# AUDIO.net
KiCad netlist of a schematic drawn in Altium Designer
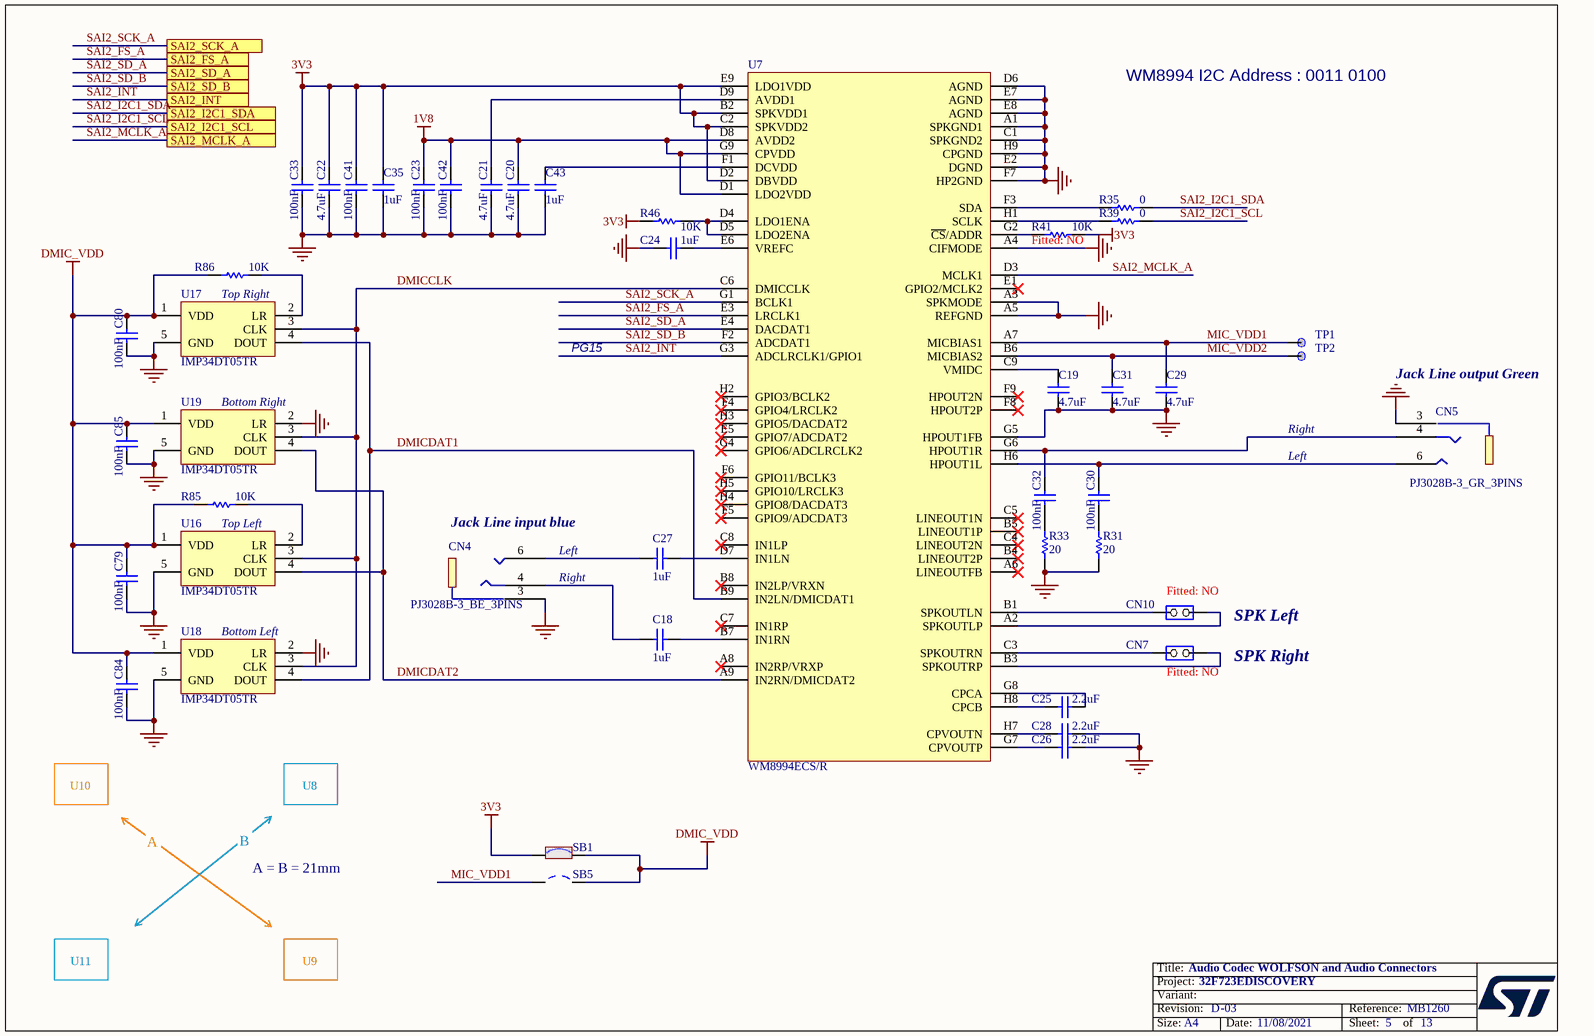
[diagram p0: AUDIO.SchDoc]

(export (version "E")
  (design (tool "Eeschema 10.0.6"))
  (components
    (comp (ref "C18")
      (value "1uF")
      (footprint "0603C")
      (description "Capacitor,1uF,16V,X5R,10%,0603,YAGEO")
      (libsource (lib "MCD_TOOLS_CAPACITOR") (part "Cap_1uF_X5R_10%_0603"))
    )
    (comp (ref "C19")
      (value "4.7uF")
      (footprint "0603C")
      (description "Capacitor,4.7uF,16V, X5R,10%,0603,YAGEO")
      (libsource (lib "MCD_TOOLS") (part "Cap_4.7uF_X5R_10%_0603"))
    )
    (comp (ref "C20")
      (value "4.7uF")
      (footprint "0603C")
      (description "Capacitor,4.7uF,16V, X5R,10%,0603,YAGEO")
      (libsource (lib "MCD_TOOLS") (part "Cap_4.7uF_X5R_10%_0603"))
    )
    (comp (ref "C21")
      (value "4.7uF")
      (footprint "0603C")
      (description "Capacitor,4.7uF,16V, X5R,10%,0603,YAGEO")
      (libsource (lib "MCD_TOOLS") (part "Cap_4.7uF_X5R_10%_0603"))
    )
    (comp (ref "C22")
      (value "4.7uF")
      (footprint "0603C")
      (description "Capacitor,4.7uF,16V, X5R,10%,0603,YAGEO")
      (libsource (lib "MCD_TOOLS") (part "Cap_4.7uF_X5R_10%_0603"))
    )
    (comp (ref "C23")
      (value "100nF")
      (footprint "0402C")
      (description "Capacitor,100nF,16V,X7R,10%,0402,YAGEO")
      (libsource (lib "MCD_TOOLS") (part "Cap_100nF_X7R_10%_0402"))
    )
    (comp (ref "C24")
      (value "1uF")
      (footprint "0603C")
      (description "Capacitor,1uF,16V,X5R,10%,0603,YAGEO")
      (libsource (lib "MCD_TOOLS_CAPACITOR") (part "Cap_1uF_X5R_10%_0603"))
    )
    (comp (ref "C25")
      (value "2.2uF")
      (footprint "0603C")
      (description "Capacitor,2.2uF,10V, X5R,10%,0603,YAGEO")
      (fields (field (name "Comment") "2.2uF_X5R_10%_0603"))
      (libsource (lib "MCD_TOOLS_CAPACITOR") (part "Cap_2.2uF_X5R_10%_0603"))
    )
    (comp (ref "C26")
      (value "2.2uF")
      (footprint "0603C")
      (description "Capacitor,2.2uF,10V, X5R,10%,0603,YAGEO")
      (fields (field (name "Comment") "2.2uF_X5R_10%_0603"))
      (libsource (lib "MCD_TOOLS_CAPACITOR") (part "Cap_2.2uF_X5R_10%_0603"))
    )
    (comp (ref "C27")
      (value "1uF")
      (footprint "0603C")
      (description "Capacitor,1uF,16V,X5R,10%,0603,YAGEO")
      (libsource (lib "MCD_TOOLS_CAPACITOR") (part "Cap_1uF_X5R_10%_0603"))
    )
    (comp (ref "C28")
      (value "2.2uF")
      (footprint "0603C")
      (description "Capacitor,2.2uF,10V, X5R,10%,0603,YAGEO")
      (fields (field (name "Comment") "2.2uF_X5R_10%_0603"))
      (libsource (lib "MCD_TOOLS_CAPACITOR") (part "Cap_2.2uF_X5R_10%_0603"))
    )
    (comp (ref "C29")
      (value "4.7uF")
      (footprint "0603C")
      (description "Capacitor,4.7uF,16V, X5R,10%,0603,YAGEO")
      (libsource (lib "MCD_TOOLS") (part "Cap_4.7uF_X5R_10%_0603"))
    )
    (comp (ref "C30")
      (value "100nF")
      (footprint "0402C")
      (description "Capacitor,100nF,16V,X7R,10%,0402,YAGEO")
      (libsource (lib "MCD_TOOLS") (part "Cap_100nF_X7R_10%_0402"))
    )
    (comp (ref "C31")
      (value "4.7uF")
      (footprint "0603C")
      (description "Capacitor,4.7uF,16V, X5R,10%,0603,YAGEO")
      (libsource (lib "MCD_TOOLS") (part "Cap_4.7uF_X5R_10%_0603"))
    )
    (comp (ref "C32")
      (value "100nF")
      (footprint "0402C")
      (description "Capacitor,100nF,16V,X7R,10%,0402,YAGEO")
      (libsource (lib "MCD_TOOLS") (part "Cap_100nF_X7R_10%_0402"))
    )
    (comp (ref "C33")
      (value "100nF")
      (footprint "0402C")
      (description "Capacitor,100nF,16V,X7R,10%,0402,YAGEO")
      (libsource (lib "MCD_TOOLS") (part "Cap_100nF_X7R_10%_0402"))
    )
    (comp (ref "C35")
      (value "1uF")
      (footprint "0603C")
      (description "Capacitor,1uF,16V,X5R,10%,0603,YAGEO")
      (libsource (lib "MCD_TOOLS_CAPACITOR") (part "Cap_1uF_X5R_10%_0603"))
    )
    (comp (ref "C41")
      (value "100nF")
      (footprint "0402C")
      (description "Capacitor,100nF,16V,X7R,10%,0402,YAGEO")
      (libsource (lib "MCD_TOOLS") (part "Cap_100nF_X7R_10%_0402"))
    )
    (comp (ref "C42")
      (value "100nF")
      (footprint "0402C")
      (description "Capacitor,100nF,16V,X7R,10%,0402,YAGEO")
      (libsource (lib "MCD_TOOLS") (part "Cap_100nF_X7R_10%_0402"))
    )
    (comp (ref "C43")
      (value "1uF")
      (footprint "0603C")
      (description "Capacitor,1uF,16V,X5R,10%,0603,YAGEO")
      (libsource (lib "MCD_TOOLS_CAPACITOR") (part "Cap_1uF_X5R_10%_0603"))
    )
    (comp (ref "C79")
      (value "100nF")
      (footprint "0402C")
      (description "Capacitor,100nF,16V,X7R,10%,0402,YAGEO")
      (libsource (lib "MCD_TOOLS") (part "Cap_100nF_X7R_10%_0402"))
    )
    (comp (ref "C80")
      (value "100nF")
      (footprint "0402C")
      (description "Capacitor,100nF,16V,X7R,10%,0402,YAGEO")
      (libsource (lib "MCD_TOOLS") (part "Cap_100nF_X7R_10%_0402"))
    )
    (comp (ref "C84")
      (value "100nF")
      (footprint "0402C")
      (description "Capacitor,100nF,16V,X7R,10%,0402,YAGEO")
      (libsource (lib "MCD_TOOLS") (part "Cap_100nF_X7R_10%_0402"))
    )
    (comp (ref "C85")
      (value "100nF")
      (footprint "0402C")
      (description "Capacitor,100nF,16V,X7R,10%,0402,YAGEO")
      (libsource (lib "MCD_TOOLS") (part "Cap_100nF_X7R_10%_0402"))
    )
    (comp (ref "CN4")
      (value "PJ3028B-3_BE_3PINS")
      (footprint "PJ3028B")
      (description "Connector Jack Stereo 3.5mm, female SMT, Blue (Line input)")
      (libsource (lib "MCD_TEMP_NPA") (part "PJ3028B-3_BE_3PINS"))
    )
    (comp (ref "CN5")
      (value "PJ3028B-3_GR_3PINS")
      (footprint "PJ3028B")
      (description "Connector Jack Stereo 3.5mm, female SMT, Green (Line output)")
      (libsource (lib "MCD_TEMP_NPA") (part "PJ3028B-3_GR_3PINS"))
    )
    (comp (ref "CN7")
      (value "JP2")
      (footprint "SIP2")
      (fields (field (name "FITTED") "NO"))
      (libsource (lib "MCD_TOOLS_CONNECTOR") (part "JP2"))
    )
    (comp (ref "CN10")
      (value "JP2")
      (footprint "SIP2")
      (fields (field (name "FITTED") "NO"))
      (libsource (lib "MCD_TOOLS_CONNECTOR") (part "JP2"))
    )
    (comp (ref "R31")
      (value "20")
      (footprint "0402R")
      (description "Resistor,20,0402,1%,YAGEO")
      (libsource (lib "MCD_TOOLS") (part "Res_20_1%_0402"))
    )
    (comp (ref "R33")
      (value "20")
      (footprint "0402R")
      (description "Resistor,20,0402,1%,YAGEO")
      (libsource (lib "MCD_TOOLS") (part "Res_20_1%_0402"))
    )
    (comp (ref "R35")
      (value "0")
      (footprint "0402R")
      (description "Resistor,0,0402,5%,YAGEO")
      (libsource (lib "MCD_TOOLS") (part "Res_0_5%_0402"))
    )
    (comp (ref "R39")
      (value "0")
      (footprint "0402R")
      (description "Resistor,0,0402,5%,YAGEO")
      (libsource (lib "MCD_TOOLS") (part "Res_0_5%_0402"))
    )
    (comp (ref "R41")
      (value "10K")
      (footprint "0402R")
      (description "Resistor,10K,0402,1%,YAGEO")
      (fields (field (name "FITTED") "NO"))
      (libsource (lib "MCD_TOOLS") (part "Res_10K_1%_0402"))
    )
    (comp (ref "R46")
      (value "10K")
      (footprint "0402R")
      (description "Resistor,10K,0402,1%,YAGEO")
      (libsource (lib "MCD_TOOLS") (part "Res_10K_1%_0402"))
    )
    (comp (ref "R85")
      (value "10K")
      (footprint "0402R")
      (description "Resistor,10K,0402,1%,YAGEO")
      (libsource (lib "MCD_TOOLS") (part "Res_10K_1%_0402"))
    )
    (comp (ref "R86")
      (value "10K")
      (footprint "0402R")
      (description "Resistor,10K,0402,1%,YAGEO")
      (libsource (lib "MCD_TOOLS") (part "Res_10K_1%_0402"))
    )
    (comp (ref "SB1")
      (value "Solder Bridge ON")
      (footprint "JP2_SMD")
      (libsource (lib "MCD_TOOLS") (part "SB_ON"))
    )
    (comp (ref "SB5")
      (value "Solder Bridge OFF")
      (footprint "JP2_SMD")
      (libsource (lib "MCD_TOOLS") (part "SB_OFF"))
    )
    (comp (ref "TP1")
      (value "TP")
      (footprint "TP_C40")
      (description "Test Point")
      (libsource (lib "MCD_TOOLS_CONNECTOR") (part "TP"))
    )
    (comp (ref "TP2")
      (value "TP")
      (footprint "TP_C40")
      (description "Test Point")
      (libsource (lib "MCD_TOOLS_CONNECTOR") (part "TP"))
    )
    (comp (ref "U7")
      (value "WM8994ECS/R")
      (footprint "BGA72_0R5_4R5X4")
      (description "Multi-Channel Audio Hub CODEC for Smartphones")
      (libsource (lib "MCD_TOOLS") (part "WM8994ECS/R"))
    )
    (comp (ref "U16")
      (value "IMP34DT05TR")
      (footprint "MP34DT01TR")
      (description "MEMS audio sensor, omnidirectional digital microphone")
      (libsource (lib "MCD_TOOLS_MISCELLANEOUS") (part "MP34DT01"))
    )
    (comp (ref "U17")
      (value "IMP34DT05TR")
      (footprint "MP34DT01TR")
      (description "MEMS audio sensor, omnidirectional digital microphone")
      (libsource (lib "MCD_TOOLS_MISCELLANEOUS") (part "MP34DT01"))
    )
    (comp (ref "U18")
      (value "IMP34DT05TR")
      (footprint "MP34DT01TR")
      (description "MEMS audio sensor, omnidirectional digital microphone")
      (libsource (lib "MCD_TOOLS_MISCELLANEOUS") (part "MP34DT01"))
    )
    (comp (ref "U19")
      (value "IMP34DT05TR")
      (footprint "MP34DT01TR")
      (description "MEMS audio sensor, omnidirectional digital microphone")
      (libsource (lib "MCD_TOOLS_MISCELLANEOUS") (part "MP34DT01"))
    )
  )
  (nets
    (net (code "1") (name "/DMICCLK") (class "Default")
      (node (ref "U16") (pin "3") (pinfunction "CLK_3") (pintype "passive"))
      (node (ref "U17") (pin "3") (pinfunction "CLK_3") (pintype "passive"))
      (node (ref "U18") (pin "3") (pinfunction "CLK_3") (pintype "passive"))
      (node (ref "U19") (pin "3") (pinfunction "CLK_3") (pintype "passive"))
      (node (ref "U7") (pin "C6") (pinfunction "DMICCLK_C6") (pintype "passive"))
    )
    (net (code "2") (name "/DMICDAT1") (class "Default")
      (node (ref "U17") (pin "4") (pinfunction "DOUT_4") (pintype "passive"))
      (node (ref "U18") (pin "4") (pinfunction "DOUT_4") (pintype "passive"))
      (node (ref "U7") (pin "B9") (pinfunction "IN2LN/DMICDAT1_B9") (pintype "passive"))
    )
    (net (code "3") (name "/DMICDAT2") (class "Default")
      (node (ref "U16") (pin "4") (pinfunction "DOUT_4") (pintype "passive"))
      (node (ref "U19") (pin "4") (pinfunction "DOUT_4") (pintype "passive"))
      (node (ref "U7") (pin "A9") (pinfunction "IN2RN/DMICDAT2_A9") (pintype "passive"))
    )
    (net (code "4") (name "/MIC_VDD1") (class "Default")
      (node (ref "C29") (pin "2") (pinfunction "2_2") (pintype "passive"))
      (node (ref "SB5") (pin "1") (pinfunction "1_1") (pintype "passive"))
      (node (ref "TP1") (pin "1") (pinfunction "1_1") (pintype "passive"))
      (node (ref "U7") (pin "A7") (pinfunction "MICBIAS1_A7") (pintype "passive"))
    )
    (net (code "5") (name "/MIC_VDD2") (class "Default")
      (node (ref "C31") (pin "2") (pinfunction "2_2") (pintype "passive"))
      (node (ref "TP2") (pin "1") (pinfunction "1_1") (pintype "passive"))
      (node (ref "U7") (pin "B6") (pinfunction "MICBIAS2_B6") (pintype "passive"))
    )
    (net (code "6") (name "/SAI2_FS_A") (class "Default")
      (node (ref "U7") (pin "E3") (pinfunction "LRCLK1_E3") (pintype "passive"))
    )
    (net (code "7") (name "/SAI2_I2C1_SCL") (class "Default")
      (node (ref "R39") (pin "1") (pinfunction "1_1") (pintype "passive"))
    )
    (net (code "8") (name "/SAI2_I2C1_SDA") (class "Default")
      (node (ref "R35") (pin "1") (pinfunction "1_1") (pintype "passive"))
    )
    (net (code "9") (name "/SAI2_INT") (class "Default")
      (node (ref "U7") (pin "G3") (pinfunction "ADCLRCLK1/GPIO1_G3") (pintype "passive"))
    )
    (net (code "10") (name "/SAI2_MCLK_A") (class "Default")
      (node (ref "U7") (pin "D3") (pinfunction "MCLK1_D3") (pintype "passive"))
    )
    (net (code "11") (name "/SAI2_SCK_A") (class "Default")
      (node (ref "U7") (pin "G1") (pinfunction "BCLK1_G1") (pintype "passive"))
    )
    (net (code "12") (name "/SAI2_SD_A") (class "Default")
      (node (ref "U7") (pin "E4") (pinfunction "DACDAT1_E4") (pintype "passive"))
    )
    (net (code "13") (name "/SAI2_SD_B") (class "Default")
      (node (ref "U7") (pin "F2") (pinfunction "ADCDAT1_F2") (pintype "passive"))
    )
    (net (code "14") (name "1V8") (class "Default")
      (node (ref "C20") (pin "1") (pinfunction "1_1") (pintype "passive"))
      (node (ref "C23") (pin "1") (pinfunction "1_1") (pintype "passive"))
      (node (ref "C42") (pin "1") (pinfunction "1_1") (pintype "passive"))
      (node (ref "U7") (pin "D1") (pinfunction "LDO2VDD_D1") (pintype "passive"))
      (node (ref "U7") (pin "D8") (pinfunction "AVDD2_D8") (pintype "passive"))
      (node (ref "U7") (pin "G9") (pinfunction "CPVDD_G9") (pintype "passive"))
    )
    (net (code "15") (name "3V3") (class "Default")
      (node (ref "C22") (pin "1") (pinfunction "1_1") (pintype "passive"))
      (node (ref "C33") (pin "1") (pinfunction "1_1") (pintype "passive"))
      (node (ref "C35") (pin "2") (pinfunction "2_2") (pintype "passive"))
      (node (ref "C41") (pin "1") (pinfunction "1_1") (pintype "passive"))
      (node (ref "R41") (pin "1") (pinfunction "1_1") (pintype "passive"))
      (node (ref "R46") (pin "2") (pinfunction "2_2") (pintype "passive"))
      (node (ref "SB1") (pin "1") (pinfunction "1_1") (pintype "passive"))
      (node (ref "U7") (pin "B2") (pinfunction "SPKVDD1_B2") (pintype "passive"))
      (node (ref "U7") (pin "C2") (pinfunction "SPKVDD2_C2") (pintype "passive"))
      (node (ref "U7") (pin "D2") (pinfunction "DBVDD_D2") (pintype "passive"))
      (node (ref "U7") (pin "E9") (pinfunction "LDO1VDD_E9") (pintype "passive"))
    )
    (net (code "16") (name "DMIC_VDD") (class "Default")
      (node (ref "C79") (pin "1") (pinfunction "1_1") (pintype "passive"))
      (node (ref "C80") (pin "1") (pinfunction "1_1") (pintype "passive"))
      (node (ref "C84") (pin "1") (pinfunction "1_1") (pintype "passive"))
      (node (ref "C85") (pin "1") (pinfunction "1_1") (pintype "passive"))
      (node (ref "R85") (pin "2") (pinfunction "2_2") (pintype "passive"))
      (node (ref "R86") (pin "2") (pinfunction "2_2") (pintype "passive"))
      (node (ref "SB1") (pin "2") (pinfunction "2_2") (pintype "passive"))
      (node (ref "SB5") (pin "2") (pinfunction "2_2") (pintype "passive"))
      (node (ref "U16") (pin "1") (pinfunction "VDD_1") (pintype "passive"))
      (node (ref "U17") (pin "1") (pinfunction "VDD_1") (pintype "passive"))
      (node (ref "U18") (pin "1") (pinfunction "VDD_1") (pintype "passive"))
      (node (ref "U19") (pin "1") (pinfunction "VDD_1") (pintype "passive"))
    )
    (net (code "17") (name "GND") (class "Default")
      (node (ref "C19") (pin "1") (pinfunction "1_1") (pintype "passive"))
      (node (ref "C20") (pin "2") (pinfunction "2_2") (pintype "passive"))
      (node (ref "C21") (pin "2") (pinfunction "2_2") (pintype "passive"))
      (node (ref "C22") (pin "2") (pinfunction "2_2") (pintype "passive"))
      (node (ref "C23") (pin "2") (pinfunction "2_2") (pintype "passive"))
      (node (ref "C24") (pin "2") (pinfunction "2_2") (pintype "passive"))
      (node (ref "C26") (pin "2") (pinfunction "2_2") (pintype "passive"))
      (node (ref "C28") (pin "2") (pinfunction "2_2") (pintype "passive"))
      (node (ref "C29") (pin "1") (pinfunction "1_1") (pintype "passive"))
      (node (ref "C31") (pin "1") (pinfunction "1_1") (pintype "passive"))
      (node (ref "C33") (pin "2") (pinfunction "2_2") (pintype "passive"))
      (node (ref "C35") (pin "1") (pinfunction "1_1") (pintype "passive"))
      (node (ref "C41") (pin "2") (pinfunction "2_2") (pintype "passive"))
      (node (ref "C42") (pin "2") (pinfunction "2_2") (pintype "passive"))
      (node (ref "C43") (pin "1") (pinfunction "1_1") (pintype "passive"))
      (node (ref "C79") (pin "2") (pinfunction "2_2") (pintype "passive"))
      (node (ref "C80") (pin "2") (pinfunction "2_2") (pintype "passive"))
      (node (ref "C84") (pin "2") (pinfunction "2_2") (pintype "passive"))
      (node (ref "C85") (pin "2") (pinfunction "2_2") (pintype "passive"))
      (node (ref "CN4") (pin "3") (pintype "passive"))
      (node (ref "CN5") (pin "3") (pintype "passive"))
      (node (ref "R31") (pin "2") (pinfunction "2_2") (pintype "passive"))
      (node (ref "R33") (pin "2") (pinfunction "2_2") (pintype "passive"))
      (node (ref "U16") (pin "5") (pinfunction "GND_5") (pintype "passive"))
      (node (ref "U17") (pin "5") (pinfunction "GND_5") (pintype "passive"))
      (node (ref "U18") (pin "2") (pinfunction "LR_2") (pintype "passive"))
      (node (ref "U18") (pin "5") (pinfunction "GND_5") (pintype "passive"))
      (node (ref "U19") (pin "2") (pinfunction "LR_2") (pintype "passive"))
      (node (ref "U19") (pin "5") (pinfunction "GND_5") (pintype "passive"))
      (node (ref "U7") (pin "A1") (pinfunction "SPKGND1_A1") (pintype "passive"))
      (node (ref "U7") (pin "A3") (pinfunction "SPKMODE_A3") (pintype "passive"))
      (node (ref "U7") (pin "A4") (pinfunction "CIFMODE_A4") (pintype "passive"))
      (node (ref "U7") (pin "A5") (pinfunction "REFGND_A5") (pintype "passive"))
      (node (ref "U7") (pin "C1") (pinfunction "SPKGND2_C1") (pintype "passive"))
      (node (ref "U7") (pin "D6") (pinfunction "AGND_D6") (pintype "passive"))
      (node (ref "U7") (pin "E2") (pinfunction "DGND_E2") (pintype "passive"))
      (node (ref "U7") (pin "E7") (pinfunction "AGND_E7") (pintype "passive"))
      (node (ref "U7") (pin "E8") (pinfunction "AGND_E8") (pintype "passive"))
      (node (ref "U7") (pin "F7") (pinfunction "HP2GND_F7") (pintype "passive"))
      (node (ref "U7") (pin "G5") (pinfunction "HPOUT1FB_G5") (pintype "passive"))
      (node (ref "U7") (pin "H9") (pinfunction "CPGND_H9") (pintype "passive"))
    )
    (net (code "18") (name "Net-(C18-Pad2)") (class "Default")
      (node (ref "C18") (pin "2") (pinfunction "2_2") (pintype "passive"))
      (node (ref "CN4") (pin "4") (pintype "passive"))
    )
    (net (code "19") (name "Net-(C27-Pad2)") (class "Default")
      (node (ref "C27") (pin "2") (pinfunction "2_2") (pintype "passive"))
      (node (ref "CN4") (pin "6") (pintype "passive"))
    )
    (net (code "20") (name "Net-(C30-Pad2)") (class "Default")
      (node (ref "C30") (pin "2") (pinfunction "2_2") (pintype "passive"))
      (node (ref "R31") (pin "1") (pinfunction "1_1") (pintype "passive"))
    )
    (net (code "21") (name "Net-(C32-Pad2)") (class "Default")
      (node (ref "C32") (pin "2") (pinfunction "2_2") (pintype "passive"))
      (node (ref "R33") (pin "1") (pinfunction "1_1") (pintype "passive"))
    )
    (net (code "22") (name "Net-(CN7-COMMON)") (class "Default")
      (node (ref "CN7") (pin "1") (pinfunction "COMMON_1") (pintype "passive"))
      (node (ref "U7") (pin "C3") (pinfunction "SPKOUTRN_C3") (pintype "passive"))
    )
    (net (code "23") (name "Net-(CN7-NO)") (class "Default")
      (node (ref "CN7") (pin "2") (pinfunction "NO_2") (pintype "passive"))
      (node (ref "U7") (pin "B3") (pinfunction "SPKOUTRP_B3") (pintype "passive"))
    )
    (net (code "24") (name "Net-(CN10-COMMON)") (class "Default")
      (node (ref "CN10") (pin "1") (pinfunction "COMMON_1") (pintype "passive"))
      (node (ref "U7") (pin "B1") (pinfunction "SPKOUTLN_B1") (pintype "passive"))
    )
    (net (code "25") (name "Net-(CN10-NO)") (class "Default")
      (node (ref "CN10") (pin "2") (pinfunction "NO_2") (pintype "passive"))
      (node (ref "U7") (pin "A2") (pinfunction "SPKOUTLP_A2") (pintype "passive"))
    )
    (net (code "26") (name "Net-(U7-AVDD1)") (class "Default")
      (node (ref "C21") (pin "1") (pinfunction "1_1") (pintype "passive"))
      (node (ref "U7") (pin "D9") (pinfunction "AVDD1_D9") (pintype "passive"))
    )
    (net (code "27") (name "Net-(U7-CPCA)") (class "Default")
      (node (ref "C25") (pin "2") (pinfunction "2_2") (pintype "passive"))
      (node (ref "U7") (pin "G8") (pinfunction "CPCA_G8") (pintype "passive"))
    )
    (net (code "28") (name "Net-(U7-CPCB)") (class "Default")
      (node (ref "C25") (pin "1") (pinfunction "1_1") (pintype "passive"))
      (node (ref "U7") (pin "H8") (pinfunction "CPCB_H8") (pintype "passive"))
    )
    (net (code "29") (name "Net-(U7-CPVOUTN)") (class "Default")
      (node (ref "C28") (pin "1") (pinfunction "1_1") (pintype "passive"))
      (node (ref "U7") (pin "H7") (pinfunction "CPVOUTN_H7") (pintype "passive"))
    )
    (net (code "30") (name "Net-(U7-CPVOUTP)") (class "Default")
      (node (ref "C26") (pin "1") (pinfunction "1_1") (pintype "passive"))
      (node (ref "U7") (pin "G7") (pinfunction "CPVOUTP_G7") (pintype "passive"))
    )
    (net (code "31") (name "Net-(U7-DCVDD)") (class "Default")
      (node (ref "C43") (pin "2") (pinfunction "2_2") (pintype "passive"))
      (node (ref "U7") (pin "F1") (pinfunction "DCVDD_F1") (pintype "passive"))
    )
    (net (code "32") (name "Net-(U7-HPOUT1L)") (class "Default")
      (node (ref "C30") (pin "1") (pinfunction "1_1") (pintype "passive"))
      (node (ref "CN5") (pin "6") (pintype "passive"))
      (node (ref "U7") (pin "H6") (pinfunction "HPOUT1L_H6") (pintype "passive"))
    )
    (net (code "33") (name "Net-(U7-HPOUT1R)") (class "Default")
      (node (ref "C32") (pin "1") (pinfunction "1_1") (pintype "passive"))
      (node (ref "CN5") (pin "4") (pintype "passive"))
      (node (ref "U7") (pin "G6") (pinfunction "HPOUT1R_G6") (pintype "passive"))
    )
    (net (code "34") (name "Net-(U7-IN1LN)") (class "Default")
      (node (ref "C27") (pin "1") (pinfunction "1_1") (pintype "passive"))
      (node (ref "U7") (pin "D7") (pinfunction "IN1LN_D7") (pintype "passive"))
    )
    (net (code "35") (name "Net-(U7-IN1RN)") (class "Default")
      (node (ref "C18") (pin "1") (pinfunction "1_1") (pintype "passive"))
      (node (ref "U7") (pin "B7") (pinfunction "IN1RN_B7") (pintype "passive"))
    )
    (net (code "36") (name "Net-(U7-LDO1ENA)") (class "Default")
      (node (ref "R46") (pin "1") (pinfunction "1_1") (pintype "passive"))
      (node (ref "U7") (pin "D4") (pinfunction "LDO1ENA_D4") (pintype "passive"))
      (node (ref "U7") (pin "D5") (pinfunction "LDO2ENA_D5") (pintype "passive"))
    )
    (net (code "37") (name "Net-(U7-SCLK)") (class "Default")
      (node (ref "R39") (pin "2") (pinfunction "2_2") (pintype "passive"))
      (node (ref "U7") (pin "H1") (pinfunction "SCLK_H1") (pintype "passive"))
    )
    (net (code "38") (name "Net-(U7-SDA)") (class "Default")
      (node (ref "R35") (pin "2") (pinfunction "2_2") (pintype "passive"))
      (node (ref "U7") (pin "F3") (pinfunction "SDA_F3") (pintype "passive"))
    )
    (net (code "39") (name "Net-(U7-VMIDC)") (class "Default")
      (node (ref "C19") (pin "2") (pinfunction "2_2") (pintype "passive"))
      (node (ref "U7") (pin "C9") (pinfunction "VMIDC_C9") (pintype "passive"))
    )
    (net (code "40") (name "Net-(U7-VREFC)") (class "Default")
      (node (ref "C24") (pin "1") (pinfunction "1_1") (pintype "passive"))
      (node (ref "U7") (pin "E6") (pinfunction "VREFC_E6") (pintype "passive"))
    )
    (net (code "41") (name "Net-(U7-~{CS}{slash}ADDR)") (class "Default")
      (node (ref "R41") (pin "2") (pinfunction "2_2") (pintype "passive"))
      (node (ref "U7") (pin "G2") (pinfunction "~{CS}/ADDR_G2") (pintype "passive"))
    )
    (net (code "42") (name "Net-(U16-LR)") (class "Default")
      (node (ref "R85") (pin "1") (pinfunction "1_1") (pintype "passive"))
      (node (ref "U16") (pin "2") (pinfunction "LR_2") (pintype "passive"))
    )
    (net (code "43") (name "Net-(U17-LR)") (class "Default")
      (node (ref "R86") (pin "1") (pinfunction "1_1") (pintype "passive"))
      (node (ref "U17") (pin "2") (pinfunction "LR_2") (pintype "passive"))
    )
    (net (code "44") (name "unconnected-(U7-GPIO2{slash}MCLK2-PadE1)") (class "Default")
      (node (ref "U7") (pin "E1") (pinfunction "GPIO2/MCLK2_E1") (pintype "passive+no_connect"))
    )
    (net (code "45") (name "unconnected-(U7-GPIO3{slash}BCLK2-PadH2)") (class "Default")
      (node (ref "U7") (pin "H2") (pinfunction "GPIO3/BCLK2_H2") (pintype "passive+no_connect"))
    )
    (net (code "46") (name "unconnected-(U7-GPIO4{slash}LRCLK2-PadF4)") (class "Default")
      (node (ref "U7") (pin "F4") (pinfunction "GPIO4/LRCLK2_F4") (pintype "passive+no_connect"))
    )
    (net (code "47") (name "unconnected-(U7-GPIO5{slash}DACDAT2-PadH3)") (class "Default")
      (node (ref "U7") (pin "H3") (pinfunction "GPIO5/DACDAT2_H3") (pintype "passive+no_connect"))
    )
    (net (code "48") (name "unconnected-(U7-GPIO6{slash}ADCLRCLK2-PadG4)") (class "Default")
      (node (ref "U7") (pin "G4") (pinfunction "GPIO6/ADCLRCLK2_G4") (pintype "passive+no_connect"))
    )
    (net (code "49") (name "unconnected-(U7-GPIO7{slash}ADCDAT2-PadE5)") (class "Default")
      (node (ref "U7") (pin "E5") (pinfunction "GPIO7/ADCDAT2_E5") (pintype "passive+no_connect"))
    )
    (net (code "50") (name "unconnected-(U7-GPIO8{slash}DACDAT3-PadH4)") (class "Default")
      (node (ref "U7") (pin "H4") (pinfunction "GPIO8/DACDAT3_H4") (pintype "passive+no_connect"))
    )
    (net (code "51") (name "unconnected-(U7-GPIO9{slash}ADCDAT3-PadF5)") (class "Default")
      (node (ref "U7") (pin "F5") (pinfunction "GPIO9/ADCDAT3_F5") (pintype "passive+no_connect"))
    )
    (net (code "52") (name "unconnected-(U7-GPIO10{slash}LRCLK3-PadH5)") (class "Default")
      (node (ref "U7") (pin "H5") (pinfunction "GPIO10/LRCLK3_H5") (pintype "passive+no_connect"))
    )
    (net (code "53") (name "unconnected-(U7-GPIO11{slash}BCLK3-PadF6)") (class "Default")
      (node (ref "U7") (pin "F6") (pinfunction "GPIO11/BCLK3_F6") (pintype "passive+no_connect"))
    )
    (net (code "54") (name "unconnected-(U7-HPOUT2N-PadF9)") (class "Default")
      (node (ref "U7") (pin "F9") (pinfunction "HPOUT2N_F9") (pintype "passive+no_connect"))
    )
    (net (code "55") (name "unconnected-(U7-HPOUT2P-PadF8)") (class "Default")
      (node (ref "U7") (pin "F8") (pinfunction "HPOUT2P_F8") (pintype "passive+no_connect"))
    )
    (net (code "56") (name "unconnected-(U7-IN1LP-PadC8)") (class "Default")
      (node (ref "U7") (pin "C8") (pinfunction "IN1LP_C8") (pintype "passive+no_connect"))
    )
    (net (code "57") (name "unconnected-(U7-IN1RP-PadC7)") (class "Default")
      (node (ref "U7") (pin "C7") (pinfunction "IN1RP_C7") (pintype "passive+no_connect"))
    )
    (net (code "58") (name "unconnected-(U7-IN2LP{slash}VRXN-PadB8)") (class "Default")
      (node (ref "U7") (pin "B8") (pinfunction "IN2LP/VRXN_B8") (pintype "passive+no_connect"))
    )
    (net (code "59") (name "unconnected-(U7-IN2RP{slash}VRXP-PadA8)") (class "Default")
      (node (ref "U7") (pin "A8") (pinfunction "IN2RP/VRXP_A8") (pintype "passive+no_connect"))
    )
    (net (code "60") (name "unconnected-(U7-LINEOUT1N-PadC5)") (class "Default")
      (node (ref "U7") (pin "C5") (pinfunction "LINEOUT1N_C5") (pintype "passive+no_connect"))
    )
    (net (code "61") (name "unconnected-(U7-LINEOUT1P-PadB5)") (class "Default")
      (node (ref "U7") (pin "B5") (pinfunction "LINEOUT1P_B5") (pintype "passive+no_connect"))
    )
    (net (code "62") (name "unconnected-(U7-LINEOUT2N-PadC4)") (class "Default")
      (node (ref "U7") (pin "C4") (pinfunction "LINEOUT2N_C4") (pintype "passive+no_connect"))
    )
    (net (code "63") (name "unconnected-(U7-LINEOUT2P-PadB4)") (class "Default")
      (node (ref "U7") (pin "B4") (pinfunction "LINEOUT2P_B4") (pintype "passive+no_connect"))
    )
    (net (code "64") (name "unconnected-(U7-LINEOUTFB-PadA6)") (class "Default")
      (node (ref "U7") (pin "A6") (pinfunction "LINEOUTFB_A6") (pintype "passive+no_connect"))
    )
  )
)
